# ADSR_7555_CTRL.net
KiCad netlist of a schematic drawn in EAGLE
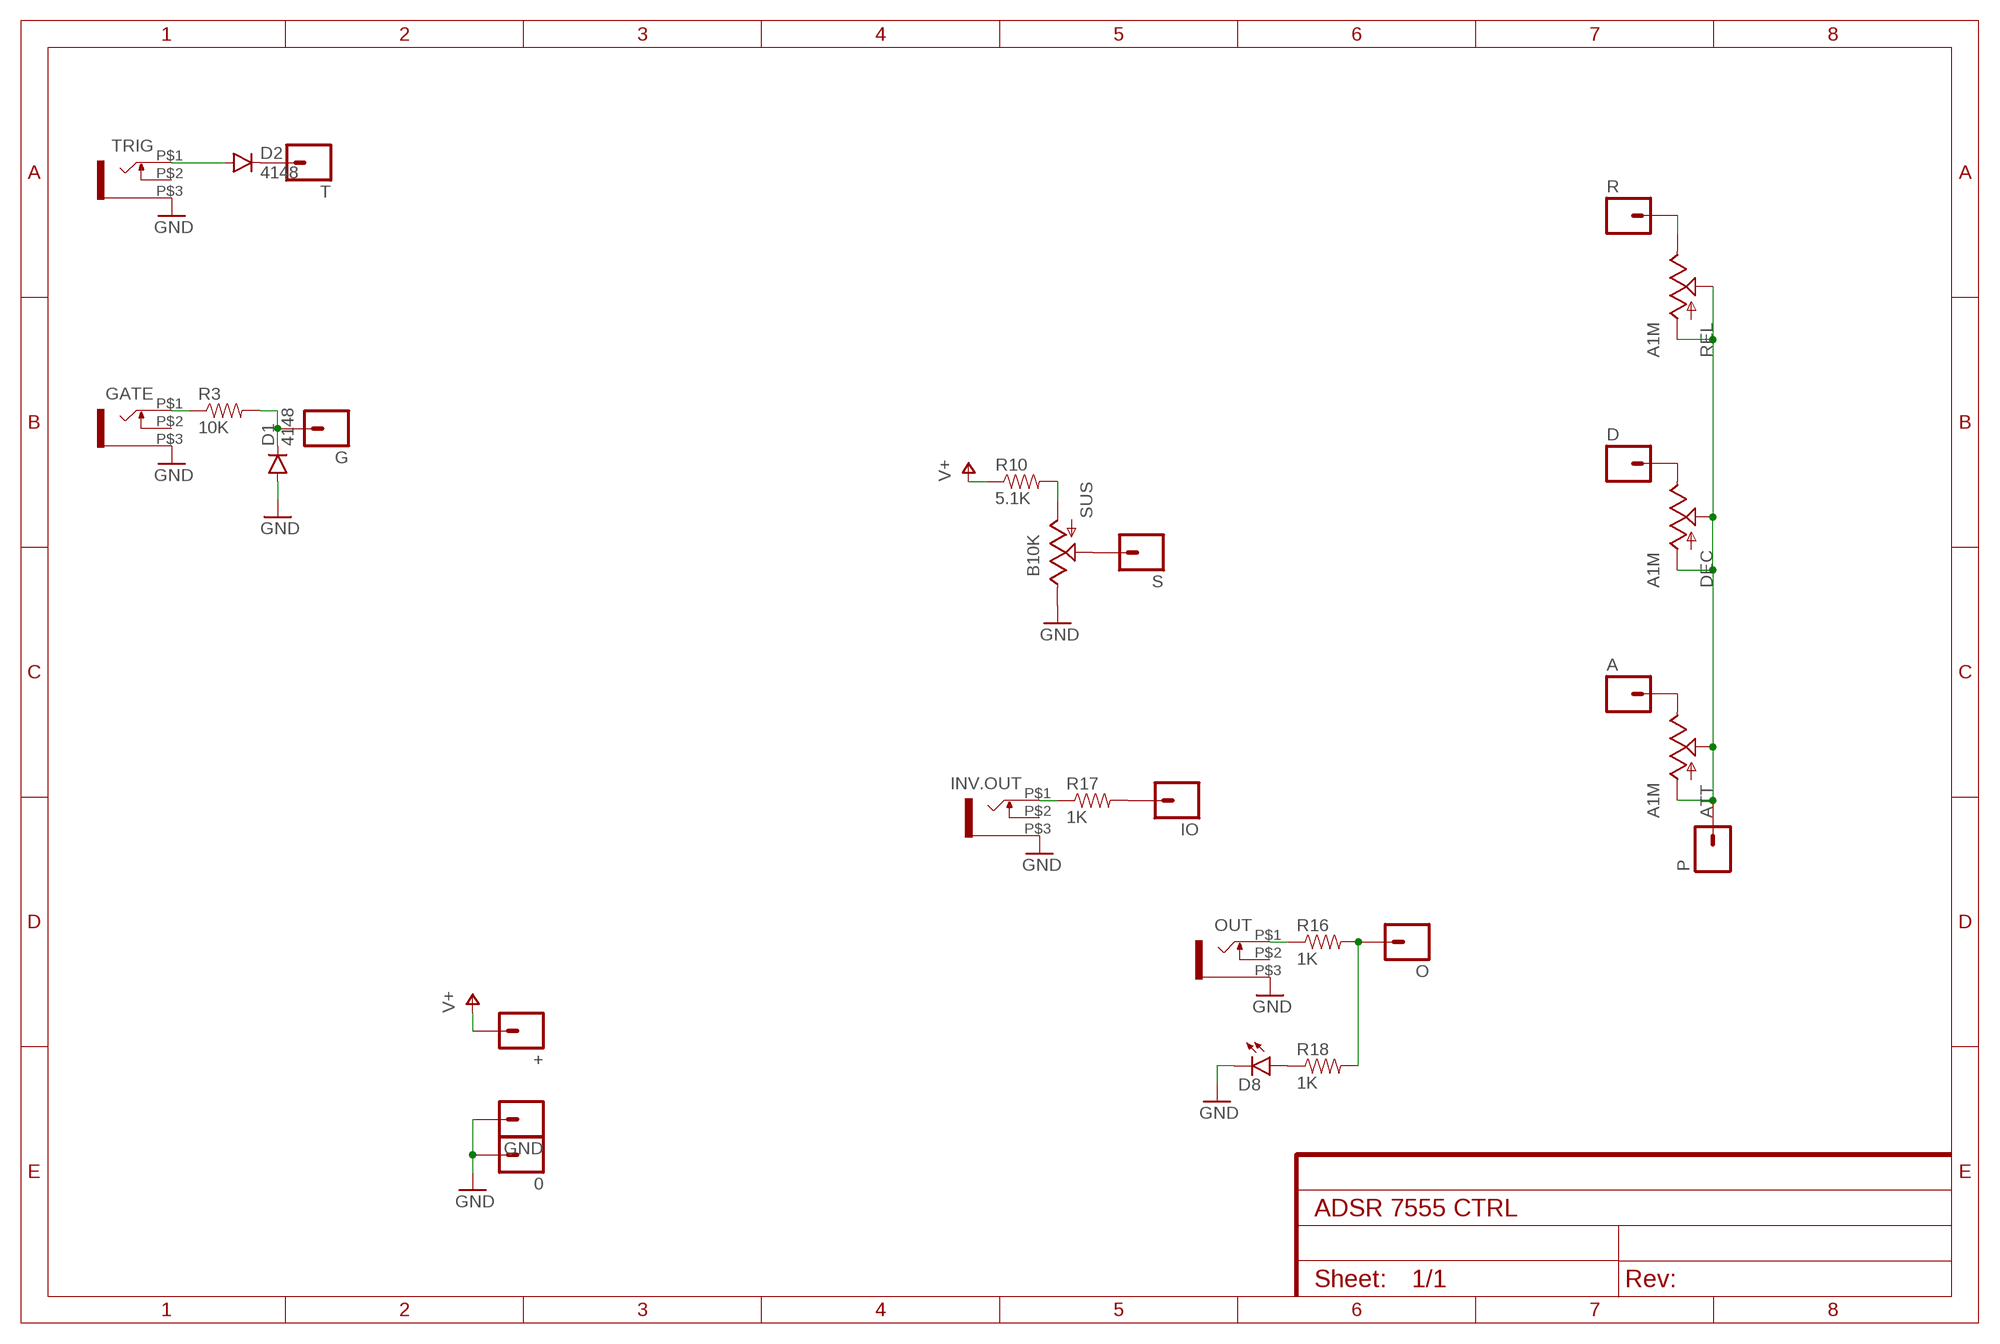
[diagram p0: schematic, sheet 1]

(export (version "E")
  (design (tool "Eeschema 10.0.6"))
  (components
    (comp (ref "+")
      (value "M01PTH")
      (footprint "eagle-import:1X01")
      (libsource (lib "eagle-import") (part "M01PTH"))
    )
    (comp (ref "0")
      (value "M01PTH")
      (footprint "eagle-import:1X01")
      (libsource (lib "eagle-import") (part "M01PTH"))
    )
    (comp (ref "A")
      (value "M01PTH")
      (footprint "eagle-import:1X01")
      (libsource (lib "eagle-import") (part "M01PTH"))
    )
    (comp (ref "ATT")
      (value "A1M")
      (footprint "eagle-import:ALPS_POT")
      (libsource (lib "eagle-import") (part "POT"))
    )
    (comp (ref "D")
      (value "M01PTH")
      (footprint "eagle-import:1X01")
      (libsource (lib "eagle-import") (part "M01PTH"))
    )
    (comp (ref "D1")
      (value "4148")
      (footprint "eagle-import:SOD-123")
      (libsource (lib "eagle-import") (part "DIODESOD123"))
    )
    (comp (ref "D2")
      (value "4148")
      (footprint "eagle-import:SOD-123")
      (libsource (lib "eagle-import") (part "DIODESOD123"))
    )
    (comp (ref "D8")
      (value "LED3MM")
      (footprint "eagle-import:LED3MM")
      (libsource (lib "eagle-import") (part "LED3MM"))
    )
    (comp (ref "DEC")
      (value "A1M")
      (footprint "eagle-import:ALPS_POT")
      (libsource (lib "eagle-import") (part "POT"))
    )
    (comp (ref "G")
      (value "M01PTH")
      (footprint "eagle-import:1X01")
      (libsource (lib "eagle-import") (part "M01PTH"))
    )
    (comp (ref "GATE")
      (value "WQP-PJ301M-12_JACK")
      (footprint "eagle-import:WQP-PJ301M-12_JACK")
      (libsource (lib "eagle-import") (part "WQP-PJ301M-12_JACK"))
    )
    (comp (ref "GND")
      (value "M01PTH")
      (footprint "eagle-import:1X01")
      (libsource (lib "eagle-import") (part "M01PTH"))
    )
    (comp (ref "INV.OUT")
      (value "WQP-PJ301M-12_JACK")
      (footprint "eagle-import:WQP-PJ301M-12_JACK")
      (libsource (lib "eagle-import") (part "WQP-PJ301M-12_JACK"))
    )
    (comp (ref "IO")
      (value "M01PTH")
      (footprint "eagle-import:1X01")
      (libsource (lib "eagle-import") (part "M01PTH"))
    )
    (comp (ref "O")
      (value "M01PTH")
      (footprint "eagle-import:1X01")
      (libsource (lib "eagle-import") (part "M01PTH"))
    )
    (comp (ref "OUT")
      (value "WQP-PJ301M-12_JACK")
      (footprint "eagle-import:WQP-PJ301M-12_JACK")
      (libsource (lib "eagle-import") (part "WQP-PJ301M-12_JACK"))
    )
    (comp (ref "P")
      (value "M01PTH")
      (footprint "eagle-import:1X01")
      (libsource (lib "eagle-import") (part "M01PTH"))
    )
    (comp (ref "R")
      (value "M01PTH")
      (footprint "eagle-import:1X01")
      (libsource (lib "eagle-import") (part "M01PTH"))
    )
    (comp (ref "R3")
      (value "10K")
      (footprint "eagle-import:0805@1")
      (libsource (lib "eagle-import") (part "RESISTOR0805-RES"))
    )
    (comp (ref "R10")
      (value "5.1K")
      (footprint "eagle-import:0805@1")
      (libsource (lib "eagle-import") (part "RESISTOR0805-RES"))
    )
    (comp (ref "R16")
      (value "1K")
      (footprint "eagle-import:0805@1")
      (libsource (lib "eagle-import") (part "RESISTOR0805-RES"))
    )
    (comp (ref "R17")
      (value "1K")
      (footprint "eagle-import:0805@1")
      (libsource (lib "eagle-import") (part "RESISTOR0805-RES"))
    )
    (comp (ref "R18")
      (value "1K")
      (footprint "eagle-import:0805@1")
      (libsource (lib "eagle-import") (part "RESISTOR0805-RES"))
    )
    (comp (ref "REL")
      (value "A1M")
      (footprint "eagle-import:ALPS_POT")
      (libsource (lib "eagle-import") (part "POT"))
    )
    (comp (ref "S")
      (value "M01PTH")
      (footprint "eagle-import:1X01")
      (libsource (lib "eagle-import") (part "M01PTH"))
    )
    (comp (ref "SUS")
      (value "B10K")
      (footprint "eagle-import:ALPS_POT")
      (libsource (lib "eagle-import") (part "POT"))
    )
    (comp (ref "T")
      (value "M01PTH")
      (footprint "eagle-import:1X01")
      (libsource (lib "eagle-import") (part "M01PTH"))
    )
    (comp (ref "TRIG")
      (value "WQP-PJ301M-12_JACK")
      (footprint "eagle-import:WQP-PJ301M-12_JACK")
      (libsource (lib "eagle-import") (part "WQP-PJ301M-12_JACK"))
    )
  )
  (nets
    (net (code "1") (name "GND") (class "Default")
      (node (ref "0") (pin "1") (pinfunction "1_1") (pintype "passive"))
      (node (ref "D1") (pin "A") (pinfunction "A_A") (pintype "passive"))
      (node (ref "D8") (pin "K") (pinfunction "C_K") (pintype "passive"))
      (node (ref "GATE") (pin "P$3") (pinfunction "1_P$3") (pintype "passive"))
      (node (ref "GND") (pin "1") (pinfunction "1_1") (pintype "passive"))
      (node (ref "INV.OUT") (pin "P$3") (pinfunction "1_P$3") (pintype "passive"))
      (node (ref "OUT") (pin "P$3") (pinfunction "1_P$3") (pintype "passive"))
      (node (ref "SUS") (pin "P$1") (pinfunction "E_P$1") (pintype "passive"))
      (node (ref "TRIG") (pin "P$3") (pinfunction "1_P$3") (pintype "passive"))
    )
    (net (code "2") (name "Net-(ATT-A)") (class "Default")
      (node (ref "ATT") (pin "P$2") (pinfunction "S_P$2") (pintype "passive"))
      (node (ref "ATT") (pin "P$3") (pinfunction "A_P$3") (pintype "passive"))
      (node (ref "DEC") (pin "P$2") (pinfunction "S_P$2") (pintype "passive"))
      (node (ref "DEC") (pin "P$3") (pinfunction "A_P$3") (pintype "passive"))
      (node (ref "P") (pin "1") (pinfunction "1_1") (pintype "passive"))
      (node (ref "REL") (pin "P$2") (pinfunction "S_P$2") (pintype "passive"))
      (node (ref "REL") (pin "P$3") (pinfunction "A_P$3") (pintype "passive"))
    )
    (net (code "3") (name "Net-(ATT-E)") (class "Default")
      (node (ref "A") (pin "1") (pinfunction "1_1") (pintype "passive"))
      (node (ref "ATT") (pin "P$1") (pinfunction "E_P$1") (pintype "passive"))
    )
    (net (code "4") (name "Net-(D1-PadC)") (class "Default")
      (node (ref "D1") (pin "C") (pinfunction "C_C") (pintype "passive"))
      (node (ref "G") (pin "1") (pinfunction "1_1") (pintype "passive"))
      (node (ref "R3") (pin "2") (pinfunction "2_2") (pintype "passive"))
    )
    (net (code "5") (name "Net-(D2-PadC)") (class "Default")
      (node (ref "D2") (pin "C") (pinfunction "C_C") (pintype "passive"))
      (node (ref "T") (pin "1") (pinfunction "1_1") (pintype "passive"))
    )
    (net (code "6") (name "Net-(D8-PadA)") (class "Default")
      (node (ref "D8") (pin "A") (pinfunction "A_A") (pintype "passive"))
      (node (ref "R18") (pin "1") (pinfunction "1_1") (pintype "passive"))
    )
    (net (code "7") (name "Net-(DEC-E)") (class "Default")
      (node (ref "D") (pin "1") (pinfunction "1_1") (pintype "passive"))
      (node (ref "DEC") (pin "P$1") (pinfunction "E_P$1") (pintype "passive"))
    )
    (net (code "8") (name "Net-(GATE-2)") (class "Default")
      (node (ref "GATE") (pin "P$1") (pinfunction "2_P$1") (pintype "passive"))
      (node (ref "R3") (pin "1") (pinfunction "1_1") (pintype "passive"))
    )
    (net (code "9") (name "Net-(INV.OUT-2)") (class "Default")
      (node (ref "INV.OUT") (pin "P$1") (pinfunction "2_P$1") (pintype "passive"))
      (node (ref "R17") (pin "1") (pinfunction "1_1") (pintype "passive"))
    )
    (net (code "10") (name "Net-(IO-Pad1)") (class "Default")
      (node (ref "IO") (pin "1") (pinfunction "1_1") (pintype "passive"))
      (node (ref "R17") (pin "2") (pinfunction "2_2") (pintype "passive"))
    )
    (net (code "11") (name "Net-(O-Pad1)") (class "Default")
      (node (ref "O") (pin "1") (pinfunction "1_1") (pintype "passive"))
      (node (ref "R16") (pin "2") (pinfunction "2_2") (pintype "passive"))
      (node (ref "R18") (pin "2") (pinfunction "2_2") (pintype "passive"))
    )
    (net (code "12") (name "Net-(OUT-2)") (class "Default")
      (node (ref "OUT") (pin "P$1") (pinfunction "2_P$1") (pintype "passive"))
      (node (ref "R16") (pin "1") (pinfunction "1_1") (pintype "passive"))
    )
    (net (code "13") (name "Net-(REL-E)") (class "Default")
      (node (ref "R") (pin "1") (pinfunction "1_1") (pintype "passive"))
      (node (ref "REL") (pin "P$1") (pinfunction "E_P$1") (pintype "passive"))
    )
    (net (code "14") (name "Net-(SUS-A)") (class "Default")
      (node (ref "R10") (pin "2") (pinfunction "2_2") (pintype "passive"))
      (node (ref "SUS") (pin "P$3") (pinfunction "A_P$3") (pintype "passive"))
    )
    (net (code "15") (name "Net-(SUS-S)") (class "Default")
      (node (ref "S") (pin "1") (pinfunction "1_1") (pintype "passive"))
      (node (ref "SUS") (pin "P$2") (pinfunction "S_P$2") (pintype "passive"))
    )
    (net (code "16") (name "Net-(TRIG-2)") (class "Default")
      (node (ref "D2") (pin "A") (pinfunction "A_A") (pintype "passive"))
      (node (ref "TRIG") (pin "P$1") (pinfunction "2_P$1") (pintype "passive"))
    )
    (net (code "17") (name "V+") (class "Default")
      (node (ref "+") (pin "1") (pinfunction "1_1") (pintype "passive"))
      (node (ref "R10") (pin "1") (pinfunction "1_1") (pintype "passive"))
    )
    (net (code "18") (name "unconnected-(GATE-3-PadP$2)") (class "Default")
      (node (ref "GATE") (pin "P$2") (pinfunction "3_P$2") (pintype "passive"))
    )
    (net (code "19") (name "unconnected-(INV.OUT-3-PadP$2)") (class "Default")
      (node (ref "INV.OUT") (pin "P$2") (pinfunction "3_P$2") (pintype "passive"))
    )
    (net (code "20") (name "unconnected-(OUT-3-PadP$2)") (class "Default")
      (node (ref "OUT") (pin "P$2") (pinfunction "3_P$2") (pintype "passive"))
    )
    (net (code "21") (name "unconnected-(TRIG-3-PadP$2)") (class "Default")
      (node (ref "TRIG") (pin "P$2") (pinfunction "3_P$2") (pintype "passive"))
    )
  )
)
